# rf-fem.net
KiCad netlist of a schematic drawn in Altium Designer
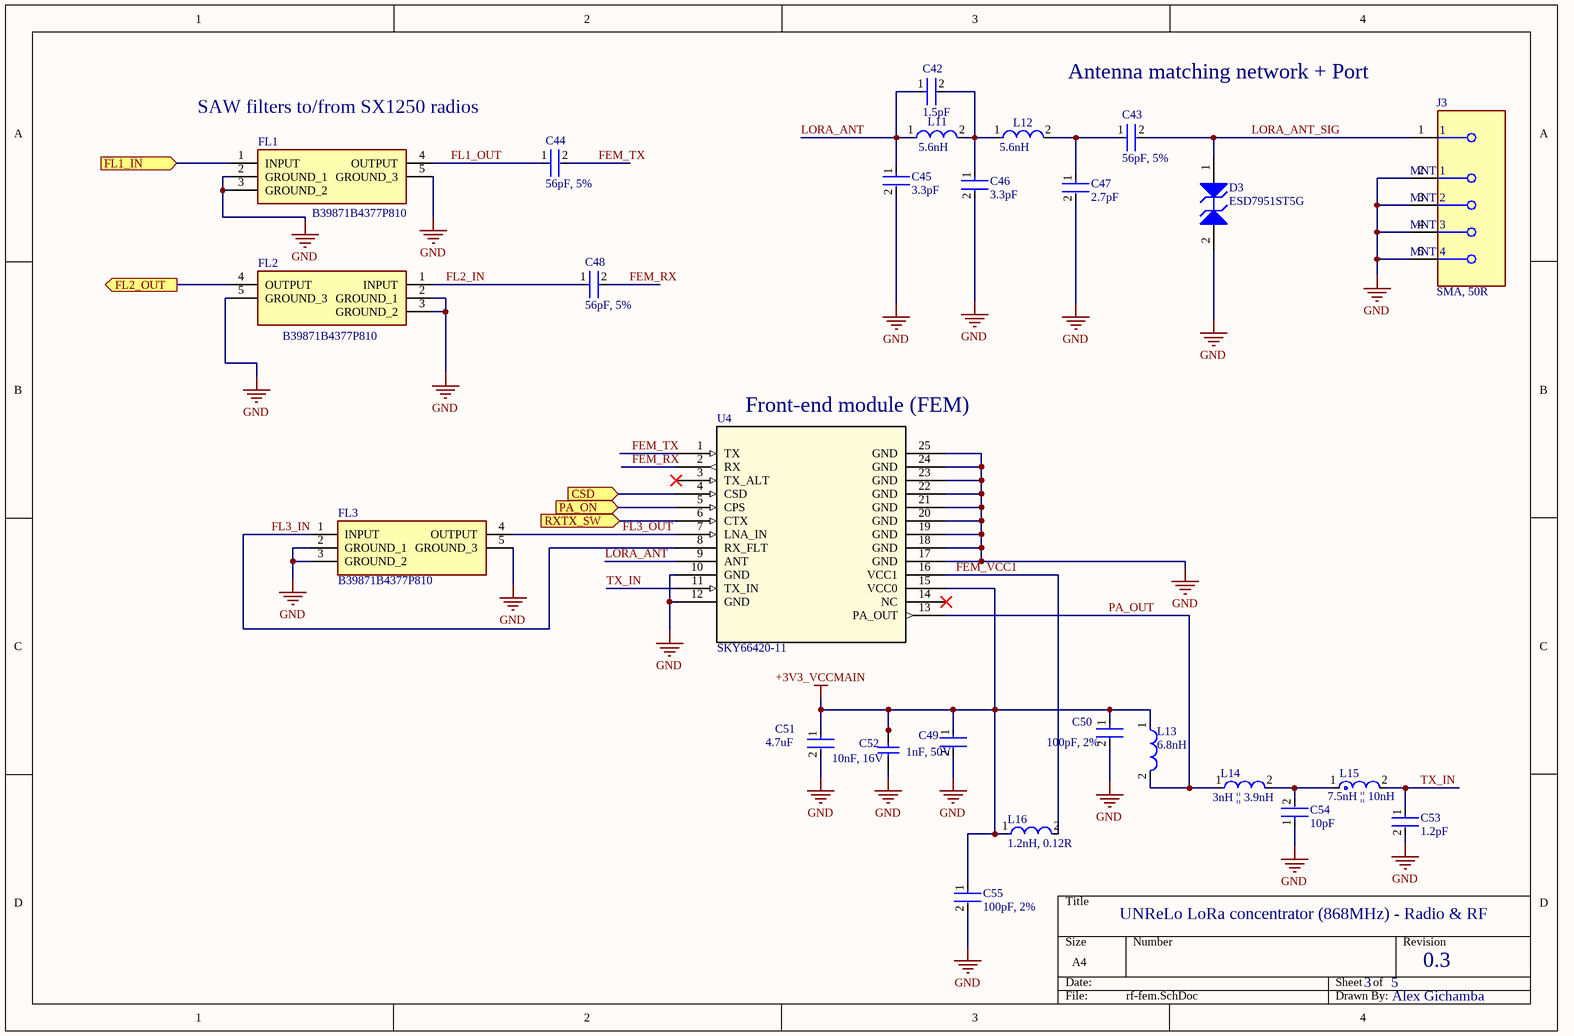
[diagram p0: rf-fem.SchDoc]

(export (version "E")
  (design (tool "Eeschema 10.0.6"))
  (components
    (comp (ref "C42")
      (value "1.5pF")
      (footprint "FP-GJM155-0_05-IPC_C")
      (description "Multi-Layer Ceramic Capacitor 1.5pF C0G  ±0.1pF 0402 Paper T/R")
      (fields (field (name "VOLTAGE") "50V"))
      (libsource (lib "Altium Content Vault") (part "02cd4be3c70576c341d710602a673aa"))
    )
    (comp (ref "C43")
      (value "56pF, 5%")
      (footprint "FP-GCM188-0_1-IPC_A")
      (description "Ceramic Capacitor for Automotive 56pF  ±5% 100VDC C0G 0603 Paper T/R")
      (fields (field (name "TOLERANCE") "5%"))
      (libsource (lib "Altium Content Vault") (part "02cd4be3c70576c341d710602a673aa"))
    )
    (comp (ref "C44")
      (value "56pF, 5%")
      (footprint "FP-GCM188-0_1-IPC_A")
      (description "Ceramic Capacitor for Automotive 56pF  ±5% 100VDC C0G 0603 Paper T/R")
      (fields (field (name "TOLERANCE") "5%"))
      (libsource (lib "Altium Content Vault") (part "02cd4be3c70576c341d710602a673aa"))
    )
    (comp (ref "C45")
      (value "3.3pF")
      (footprint "FP-GQM187-0_15-MFG")
      (description "Ceramic Capacitor 3.3pF ±0.1pF 250VDC C0G 0603 Paper T/R")
      (libsource (lib "Altium Content Vault") (part "02cd4be3c70576c341d710602a673aa"))
    )
    (comp (ref "C46")
      (value "3.3pF")
      (footprint "FP-GQM187-0_15-MFG")
      (description "Ceramic Capacitor 3.3pF ±0.1pF 250VDC C0G 0603 Paper T/R")
      (libsource (lib "Altium Content Vault") (part "02cd4be3c70576c341d710602a673aa"))
    )
    (comp (ref "C47")
      (value "2.7pF")
      (footprint "FP-CL428-IPC_C")
      (description "Cap Ceramic 2.7pF 50V C0G ±0.1pF SMD 0402 +125°C Paper T/R")
      (fields (field (name "VOLTAGE") "50V"))
      (libsource (lib "Altium Content Vault") (part "b4654b650e69147ec39a6b967a45e02"))
    )
    (comp (ref "C48")
      (value "56pF, 5%")
      (footprint "FP-GCM188-0_1-IPC_A")
      (description "Ceramic Capacitor for Automotive 56pF  ±5% 100VDC C0G 0603 Paper T/R")
      (fields (field (name "TOLERANCE") "5%"))
      (libsource (lib "Altium Content Vault") (part "02cd4be3c70576c341d710602a673aa"))
    )
    (comp (ref "C49")
      (value "1nF, 50V")
      (footprint "FP-CL10-IPC_A")
      (description "Cap Ceramic 1nF 50V C0G ±5% Pad SMD 0603 +125°C T/R")
      (fields (field (name "VOLTAGE") "50V") (field (name "TOLERANCE") "5%"))
      (libsource (lib "Altium Content Vault") (part "b4654b650e69147ec39a6b967a45e02"))
    )
    (comp (ref "C50")
      (value "100pF, 2%")
      (footprint "FP-0805-L_2_01_0_2-W_1_25-IPC_A")
      (description "General Purpose Ceramic Capacitor, 0805, 100pF, 5%, C0G, 30ppm/°C, 100V")
      (fields (field (name "TOLERANCE") "5%") (field (name "VOLTAGE") "100V"))
      (libsource (lib "Altium Content Vault") (part "02cd4be3c70576c341d710602a673aa"))
    )
    (comp (ref "C51")
      (value "4.7uF")
      (footprint "FP-CL21-IPC_A")
      (description "CL21 Series 0805 4.7uF 25V ±10% Tolerance X5R Multilayer Ceramic Chip Capacitor")
      (fields (field (name "TOLERANCE") "10%"))
      (libsource (lib "Altium Content Vault") (part "b4654b650e69147ec39a6b967a45e02"))
    )
    (comp (ref "C52")
      (value "10nF, 16V")
      (footprint "CAPC1608X90X35NL15T15")
      (fields
        (field (name "MANUFACTURER") "AVX Interconnect / Elco")
        (field (name "PART NUMBER") "0603YC103JAT2A")
      )
      (libsource (lib "Altium Content Vault") (part "CAP"))
    )
    (comp (ref "C53")
      (value "1.2pF")
      (footprint "FP-CL110-IPC_C")
      (description "Cap Ceramic 1.2pF 50V C0G ±0.25pF SMD 0402 +125°C Paper T/R")
      (fields (field (name "VOLTAGE") "50V"))
      (libsource (lib "Altium Content Vault") (part "b4654b650e69147ec39a6b967a45e02"))
    )
    (comp (ref "C54")
      (value "10pF")
      (footprint "FP-CL10-IPC_A")
      (description "Cap Ceramic 10pF 50V C0G ±5% Pad SMD 0603 +125°C T/R")
      (fields (field (name "VOLTAGE") "50V") (field (name "TOLERANCE") "5%"))
      (libsource (lib "Altium Content Vault") (part "b4654b650e69147ec39a6b967a45e02"))
    )
    (comp (ref "C55")
      (value "100pF, 2%")
      (footprint "FP-0805-L_2_01_0_2-W_1_25-IPC_A")
      (description "General Purpose Ceramic Capacitor, 0805, 100pF, 5%, C0G, 30ppm/°C, 100V")
      (fields (field (name "TOLERANCE") "5%") (field (name "VOLTAGE") "100V"))
      (libsource (lib "Altium Content Vault") (part "02cd4be3c70576c341d710602a673aa"))
    )
    (comp (ref "D3")
      (value "ESD7951ST5G")
      (footprint "ONSC-SOD-923-2-514AB-01_V")
      (fields (field (name "MANUFACTURER") "On Semiconductor"))
      (libsource (lib "Altium Content Vault") (part "ONSC-A1A2-2"))
    )
    (comp (ref "FL1")
      (value "B39871B4377P810")
      (footprint "B39871B4377P810")
      (description "Filter")
      (fields (field (name "MOUSER PART NUMBER") "871-B39871B4377P810"))
      (libsource (lib "") (part "B39871B4377P810_1"))
    )
    (comp (ref "FL2")
      (value "B39871B4377P810")
      (footprint "B39871B4377P810")
      (description "Filter")
      (fields (field (name "MOUSER PART NUMBER") "871-B39871B4377P810"))
      (libsource (lib "SamacSys") (part "B39871B4377P810"))
    )
    (comp (ref "FL3")
      (value "B39871B4377P810")
      (footprint "B39871B4377P810")
      (description "Filter")
      (fields (field (name "MOUSER PART NUMBER") "871-B39871B4377P810"))
      (libsource (lib "") (part "B39871B4377P810_1"))
    )
    (comp (ref "J3")
      (value "SMA, 50R")
      (footprint "FP-SMA-J-P-H-ST-EM1-MFG")
      (description "CONN SMA JACK STR 50OHM EDGE MNT")
      (libsource (lib "Altium Content Vault") (part "c65b8a639cdaef1819ea20b5466f8fa"))
    )
    (comp (ref "L11")
      (value "5.6nH")
      (footprint "FP-LQW18AN_80-MFG")
      (description "Wire Wound RF Inductor for Automotive 5.6nH ±2% 1900mA 0.04Ω 0603 (1608)")
      (fields (field (name "TOLERANCE") "2%"))
      (libsource (lib "Altium Content Vault") (part "725321dda6339637d4d059423bc1c3c"))
    )
    (comp (ref "L12")
      (value "5.6nH")
      (footprint "FP-LQW18AN_80-MFG")
      (description "Wire Wound RF Inductor for Automotive 5.6nH ±2% 1900mA 0.04Ω 0603 (1608)")
      (fields (field (name "TOLERANCE") "2%"))
      (libsource (lib "Altium Content Vault") (part "725321dda6339637d4d059423bc1c3c"))
    )
    (comp (ref "L13")
      (value "6.8nH")
      (footprint "FP-LQW15AN_00-W0_6-0_1-MFG")
      (description "Wire Wound RF Inductor 6.8nH ±5% 700mA 0.09Ω 0402 (1005)")
      (fields (field (name "TOLERANCE") "5%"))
      (libsource (lib "Altium Content Vault") (part "725321dda6339637d4d059423bc1c3c"))
    )
    (comp (ref "L14")
      (value "3nH Ζ 3.9nH")
      (footprint "FP-MLK1005-IPC_B")
      (description "Unshielded Multilayer Inductor 2nH ±0.3nH 500mA 0.18Ω SMD 0402")
      (libsource (lib "Altium Content Vault") (part "725321dda6339637d4d059423bc1c3c"))
    )
    (comp (ref "L15")
      (value "7.5nH Ζ 10nH")
      (footprint "FP-LQG15HH_02-IPC_A")
      (description "Multilayer type RF Inductor 10nH ±5% 0.26Ω 500mA 0402")
      (fields (field (name "TOLERANCE") "5%"))
      (libsource (lib "Altium Content Vault") (part "4cc4b267dca4c8e51f7102f422741d8"))
    )
    (comp (ref "L16")
      (value "1.2nH, 0.12R")
      (footprint "FP-MLK1005-IPC_C")
      (description "Unshielded Multilayer Inductor 1.2nH ±0.3nH 500mA 0.12Ω SMD 0402")
      (libsource (lib "Altium Content Vault") (part "725321dda6339637d4d059423bc1c3c"))
    )
    (comp (ref "U4")
      (value "SKY66420-11")
      (footprint "MCM16_3X3X0P75_SKY")
      (description "Built for UNReLo. 860 to 930 MHz RF Front-End Module")
      (fields (field (name "COPYRIGHT") "Copyright (C) 2022 Ultra Librarian. All rights reserved."))
      (libsource (lib "SKY66420-11") (part "SKY66420-11"))
    )
  )
  (nets
    (net (code "1") (name "+3V3_VCCMAIN") (class "Default")
      (node (ref "C49") (pin "1") (pinfunction "1_1") (pintype "passive"))
      (node (ref "C50") (pin "1") (pinfunction "1_1") (pintype "passive"))
      (node (ref "C51") (pin "1") (pinfunction "1_1") (pintype "passive"))
      (node (ref "C52") (pin "2") (pinfunction "2_2") (pintype "passive"))
      (node (ref "C55") (pin "1") (pinfunction "1_1") (pintype "passive"))
      (node (ref "L13") (pin "1") (pinfunction "1_1") (pintype "passive"))
      (node (ref "L16") (pin "1") (pinfunction "1_1") (pintype "passive"))
      (node (ref "U4") (pin "15") (pinfunction "VCC0_15") (pintype "power_in"))
    )
    (net (code "2") (name "/CSD") (class "Default")
      (node (ref "U4") (pin "4") (pinfunction "CSD_4") (pintype "input"))
    )
    (net (code "3") (name "/FEM_RX") (class "Default")
      (node (ref "C48") (pin "2") (pinfunction "2_2") (pintype "passive"))
      (node (ref "U4") (pin "2") (pinfunction "RX_2") (pintype "output"))
    )
    (net (code "4") (name "/FEM_TX") (class "Default")
      (node (ref "C44") (pin "2") (pinfunction "2_2") (pintype "passive"))
      (node (ref "U4") (pin "1") (pinfunction "TX_1") (pintype "input"))
    )
    (net (code "5") (name "/FEM_VCC1") (class "Default")
      (node (ref "L16") (pin "2") (pinfunction "2_2") (pintype "passive"))
      (node (ref "U4") (pin "16") (pinfunction "VCC1_16") (pintype "power_in"))
    )
    (net (code "6") (name "/FL1_IN") (class "Default")
      (node (ref "FL1") (pin "1") (pinfunction "INPUT_1") (pintype "passive"))
    )
    (net (code "7") (name "/FL1_OUT") (class "Default")
      (node (ref "C44") (pin "1") (pinfunction "1_1") (pintype "passive"))
      (node (ref "FL1") (pin "4") (pinfunction "OUTPUT_4") (pintype "passive"))
    )
    (net (code "8") (name "/FL2_IN") (class "Default")
      (node (ref "C48") (pin "1") (pinfunction "1_1") (pintype "passive"))
      (node (ref "FL2") (pin "1") (pinfunction "INPUT_1") (pintype "passive"))
    )
    (net (code "9") (name "/FL2_OUT") (class "Default")
      (node (ref "FL2") (pin "4") (pinfunction "OUTPUT_4") (pintype "passive"))
    )
    (net (code "10") (name "/FL3_IN") (class "Default")
      (node (ref "FL3") (pin "1") (pinfunction "INPUT_1") (pintype "passive"))
      (node (ref "U4") (pin "8") (pinfunction "RX_FLT_8") (pintype "passive"))
    )
    (net (code "11") (name "/FL3_OUT") (class "Default")
      (node (ref "FL3") (pin "4") (pinfunction "OUTPUT_4") (pintype "passive"))
      (node (ref "U4") (pin "7") (pinfunction "LNA_IN_7") (pintype "input"))
    )
    (net (code "12") (name "/LORA_ANT") (class "Default")
      (node (ref "C42") (pin "1") (pinfunction "1_1") (pintype "passive"))
      (node (ref "C45") (pin "1") (pinfunction "1_1") (pintype "passive"))
      (node (ref "L11") (pin "1") (pinfunction "1_1") (pintype "passive"))
      (node (ref "U4") (pin "9") (pinfunction "ANT_9") (pintype "passive"))
    )
    (net (code "13") (name "/LORA_ANT_SIG") (class "Default")
      (node (ref "C43") (pin "2") (pinfunction "2_2") (pintype "passive"))
      (node (ref "D3") (pin "1") (pinfunction "A1_1") (pintype "passive"))
      (node (ref "J3") (pin "1") (pinfunction "1_1") (pintype "passive"))
    )
    (net (code "14") (name "/PA_ON") (class "Default")
      (node (ref "U4") (pin "5") (pinfunction "CPS_5") (pintype "input"))
    )
    (net (code "15") (name "/PA_OUT") (class "Default")
      (node (ref "L13") (pin "2") (pinfunction "2_2") (pintype "passive"))
      (node (ref "L14") (pin "1") (pinfunction "1_1") (pintype "passive"))
      (node (ref "U4") (pin "13") (pinfunction "PA_OUT_13") (pintype "output"))
    )
    (net (code "16") (name "/RXTX_SW") (class "Default")
      (node (ref "U4") (pin "6") (pinfunction "CTX_6") (pintype "input"))
    )
    (net (code "17") (name "/TX_IN") (class "Default")
      (node (ref "C53") (pin "1") (pinfunction "1_1") (pintype "passive"))
      (node (ref "L15") (pin "2") (pinfunction "2_2") (pintype "passive"))
      (node (ref "U4") (pin "11") (pinfunction "TX_IN_11") (pintype "input"))
    )
    (net (code "18") (name "GND") (class "Default")
      (node (ref "C45") (pin "2") (pinfunction "2_2") (pintype "passive"))
      (node (ref "C46") (pin "2") (pinfunction "2_2") (pintype "passive"))
      (node (ref "C47") (pin "2") (pinfunction "2_2") (pintype "passive"))
      (node (ref "C49") (pin "2") (pinfunction "2_2") (pintype "passive"))
      (node (ref "C50") (pin "2") (pinfunction "2_2") (pintype "passive"))
      (node (ref "C51") (pin "2") (pinfunction "2_2") (pintype "passive"))
      (node (ref "C52") (pin "1") (pinfunction "1_1") (pintype "passive"))
      (node (ref "C53") (pin "2") (pinfunction "2_2") (pintype "passive"))
      (node (ref "C54") (pin "1") (pinfunction "1_1") (pintype "passive"))
      (node (ref "C55") (pin "2") (pinfunction "2_2") (pintype "passive"))
      (node (ref "D3") (pin "2") (pinfunction "A2_2") (pintype "passive"))
      (node (ref "FL1") (pin "2") (pinfunction "GROUND_1_2") (pintype "passive"))
      (node (ref "FL1") (pin "3") (pinfunction "GROUND_2_3") (pintype "passive"))
      (node (ref "FL1") (pin "5") (pinfunction "GROUND_3_5") (pintype "passive"))
      (node (ref "FL2") (pin "2") (pinfunction "GROUND_1_2") (pintype "passive"))
      (node (ref "FL2") (pin "3") (pinfunction "GROUND_2_3") (pintype "passive"))
      (node (ref "FL2") (pin "5") (pinfunction "GROUND_3_5") (pintype "passive"))
      (node (ref "FL3") (pin "2") (pinfunction "GROUND_1_2") (pintype "passive"))
      (node (ref "FL3") (pin "3") (pinfunction "GROUND_2_3") (pintype "passive"))
      (node (ref "FL3") (pin "5") (pinfunction "GROUND_3_5") (pintype "passive"))
      (node (ref "J3") (pin "2") (pinfunction "MNT_1_2") (pintype "passive"))
      (node (ref "J3") (pin "3") (pinfunction "MNT_2_3") (pintype "passive"))
      (node (ref "J3") (pin "4") (pinfunction "MNT_3_4") (pintype "passive"))
      (node (ref "J3") (pin "5") (pinfunction "MNT_4_5") (pintype "passive"))
      (node (ref "U4") (pin "10") (pinfunction "GND_10") (pintype "passive"))
      (node (ref "U4") (pin "12") (pinfunction "GND_12") (pintype "passive"))
      (node (ref "U4") (pin "17") (pinfunction "GND_17") (pintype "passive"))
      (node (ref "U4") (pin "18") (pinfunction "GND_18") (pintype "passive"))
      (node (ref "U4") (pin "19") (pinfunction "GND_19") (pintype "passive"))
      (node (ref "U4") (pin "20") (pinfunction "GND_20") (pintype "passive"))
      (node (ref "U4") (pin "21") (pinfunction "GND_21") (pintype "passive"))
      (node (ref "U4") (pin "22") (pinfunction "GND_22") (pintype "passive"))
      (node (ref "U4") (pin "23") (pinfunction "GND_23") (pintype "passive"))
      (node (ref "U4") (pin "24") (pinfunction "GND_24") (pintype "passive"))
      (node (ref "U4") (pin "25") (pinfunction "GND_25") (pintype "passive"))
    )
    (net (code "19") (name "Net-(C42-Pad2)") (class "Default")
      (node (ref "C42") (pin "2") (pinfunction "2_2") (pintype "passive"))
      (node (ref "C46") (pin "1") (pinfunction "1_1") (pintype "passive"))
      (node (ref "L11") (pin "2") (pinfunction "2_2") (pintype "passive"))
      (node (ref "L12") (pin "1") (pinfunction "1_1") (pintype "passive"))
    )
    (net (code "20") (name "Net-(C43-Pad1)") (class "Default")
      (node (ref "C43") (pin "1") (pinfunction "1_1") (pintype "passive"))
      (node (ref "C47") (pin "1") (pinfunction "1_1") (pintype "passive"))
      (node (ref "L12") (pin "2") (pinfunction "2_2") (pintype "passive"))
    )
    (net (code "21") (name "Net-(C54-Pad2)") (class "Default")
      (node (ref "C54") (pin "2") (pinfunction "2_2") (pintype "passive"))
      (node (ref "L14") (pin "2") (pinfunction "2_2") (pintype "passive"))
      (node (ref "L15") (pin "1") (pinfunction "1_1") (pintype "passive"))
    )
    (net (code "22") (name "unconnected-(U4-NC-Pad14)") (class "Default")
      (node (ref "U4") (pin "14") (pinfunction "NC_14") (pintype "passive+no_connect"))
    )
    (net (code "23") (name "unconnected-(U4-TX_ALT-Pad3)") (class "Default")
      (node (ref "U4") (pin "3") (pinfunction "TX_ALT_3") (pintype "input+no_connect"))
    )
  )
)
